# Cotton_Candy_-SCH.net
KiCad netlist of a schematic drawn in Altium Designer
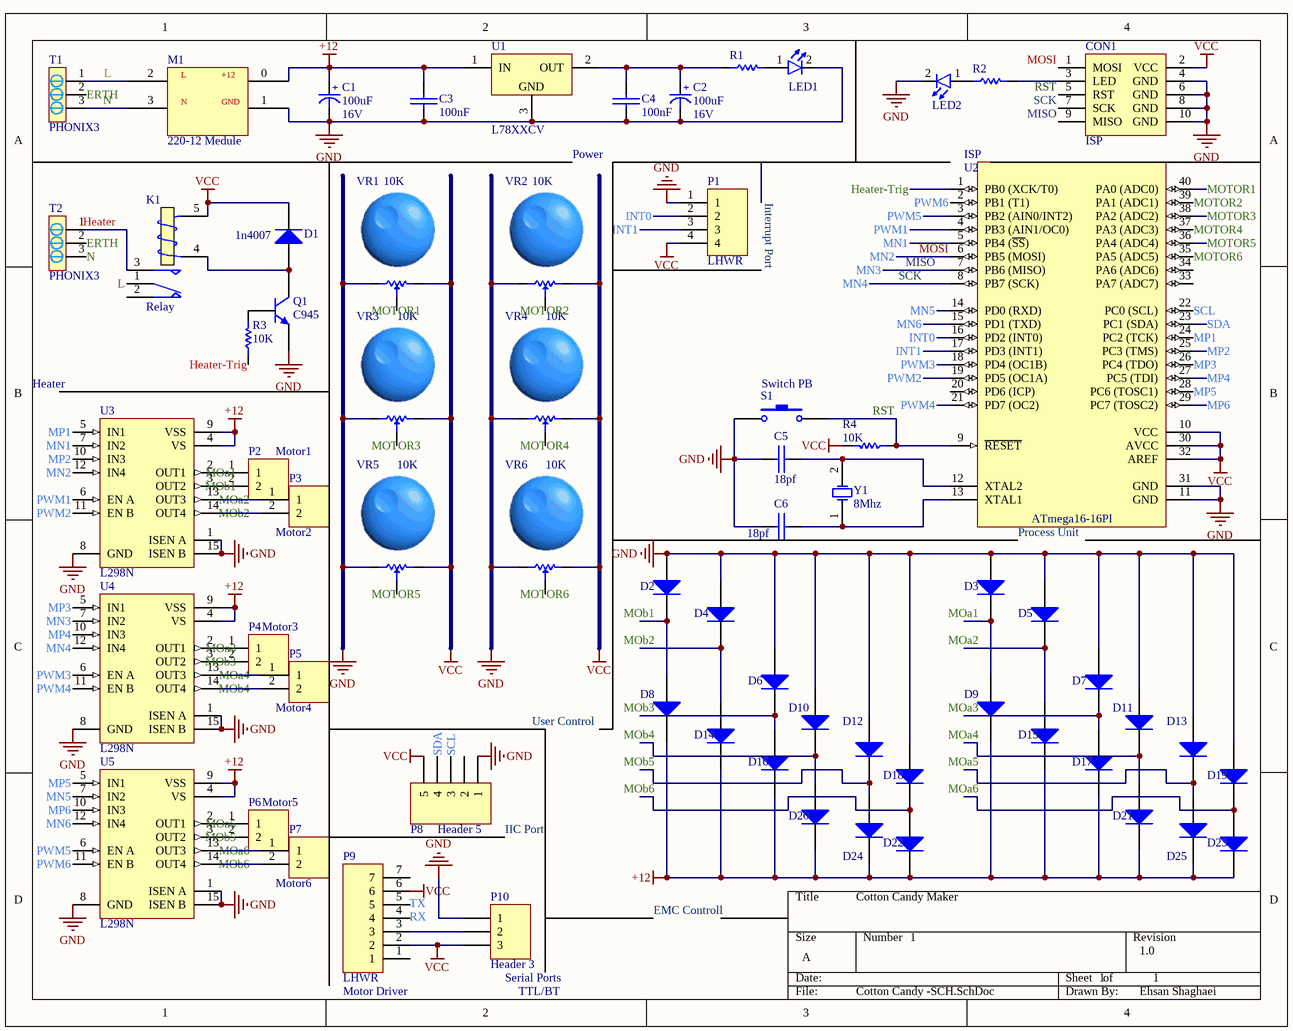
[diagram p0: Cotton Candy -SCH.SchDoc]

(export (version "E")
  (design (tool "Eeschema 10.0.6"))
  (components
    (comp (ref "C1")
      (value "100uF")
      (footprint "cap 03")
      (description "Polar Capacitor")
      (fields
        (field (name "VOLTAGE") "16V")
        (field (name "Comment") "100uf")
        (field (name "DESIGNER") "Saeid Jorablo")
      )
      (libsource (lib "My Library") (part "Cap-Polar"))
    )
    (comp (ref "C2")
      (value "100uF")
      (footprint "cap 03")
      (description "Polar Capacitor")
      (fields
        (field (name "VOLTAGE") "16V")
        (field (name "Comment") "100uf")
        (field (name "DESIGNER") "Saeid Jorablo")
      )
      (libsource (lib "My Library") (part "Cap-Polar"))
    )
    (comp (ref "C3")
      (value "100nF")
      (footprint "Cap - 10nF - 630V")
      (description "Bipolar Capacitor")
      (fields
        (field (name "VOLTAGE") "100V")
        (field (name "Comment") "100nf")
        (field (name "DESIGNER") "Saeid Jorablo")
      )
      (libsource (lib "My Library") (part "Cap-Bipolar"))
    )
    (comp (ref "C4")
      (value "100nF")
      (footprint "Cap - 10nF - 630V")
      (description "Bipolar Capacitor")
      (fields
        (field (name "VOLTAGE") "100V")
        (field (name "Comment") "100nf")
        (field (name "DESIGNER") "Saeid Jorablo")
      )
      (libsource (lib "My Library") (part "Cap-Bipolar"))
    )
    (comp (ref "C5")
      (value "18pf")
      (footprint "Cap - 10nF - 630V")
      (description "Bipolar Capacitor")
      (fields
        (field (name "VOLTAGE") "100V")
        (field (name "Comment") "22pf")
        (field (name "DESIGNER") "Saeid Jorablo")
      )
      (libsource (lib "My Library") (part "Cap-Bipolar"))
    )
    (comp (ref "C6")
      (value "18pf")
      (footprint "Cap - 10nF - 630V")
      (description "Bipolar Capacitor")
      (fields
        (field (name "VOLTAGE") "100V")
        (field (name "Comment") "22pf")
        (field (name "DESIGNER") "Saeid Jorablo")
      )
      (libsource (lib "My Library") (part "Cap-Bipolar"))
    )
    (comp (ref "CON1") (value "ISP") (footprint "IDC2_5") (libsource (lib "MyAltiumLib") (part "ISP")))
    (comp (ref "D1")
      (value "1n4007")
      (footprint "BYW98")
      (description "HIGH EFFICIENCY FAST RECOVERY RECTIFIER DIODES")
      (fields (field (name "DESIGNER") "Saeid Jorablo"))
      (libsource (lib "My Library") (part "BYW98"))
    )
    (comp (ref "D2")
      (value "~")
      (footprint "My_DO-41")
      (description "1 Amp Diode")
      (libsource (lib "Mylib") (part "1N4007"))
    )
    (comp (ref "D3")
      (value "~")
      (footprint "My_DO-41")
      (description "1 Amp Diode")
      (libsource (lib "Mylib") (part "1N4007"))
    )
    (comp (ref "D4")
      (value "~")
      (footprint "My_DO-41")
      (description "1 Amp Diode")
      (libsource (lib "Mylib") (part "1N4007"))
    )
    (comp (ref "D5")
      (value "~")
      (footprint "My_DO-41")
      (description "1 Amp Diode")
      (libsource (lib "Mylib") (part "1N4007"))
    )
    (comp (ref "D6")
      (value "~")
      (footprint "My_DO-41")
      (description "1 Amp Diode")
      (libsource (lib "Mylib") (part "1N4007"))
    )
    (comp (ref "D7")
      (value "~")
      (footprint "My_DO-41")
      (description "1 Amp Diode")
      (libsource (lib "Mylib") (part "1N4007"))
    )
    (comp (ref "D8")
      (value "~")
      (footprint "My_DO-41")
      (description "1 Amp Diode")
      (libsource (lib "Mylib") (part "1N4007"))
    )
    (comp (ref "D9")
      (value "~")
      (footprint "My_DO-41")
      (description "1 Amp Diode")
      (libsource (lib "Mylib") (part "1N4007"))
    )
    (comp (ref "D10")
      (value "~")
      (footprint "My_DO-41")
      (description "1 Amp Diode")
      (libsource (lib "Mylib") (part "1N4007"))
    )
    (comp (ref "D11")
      (value "~")
      (footprint "My_DO-41")
      (description "1 Amp Diode")
      (libsource (lib "Mylib") (part "1N4007"))
    )
    (comp (ref "D12")
      (value "~")
      (footprint "My_DO-41")
      (description "1 Amp Diode")
      (libsource (lib "Mylib") (part "1N4007"))
    )
    (comp (ref "D13")
      (value "~")
      (footprint "My_DO-41")
      (description "1 Amp Diode")
      (libsource (lib "Mylib") (part "1N4007"))
    )
    (comp (ref "D14")
      (value "~")
      (footprint "My_DO-41")
      (description "1 Amp Diode")
      (libsource (lib "Mylib") (part "1N4007"))
    )
    (comp (ref "D15")
      (value "~")
      (footprint "My_DO-41")
      (description "1 Amp Diode")
      (libsource (lib "Mylib") (part "1N4007"))
    )
    (comp (ref "D16")
      (value "~")
      (footprint "My_DO-41")
      (description "1 Amp Diode")
      (libsource (lib "Mylib") (part "1N4007"))
    )
    (comp (ref "D17")
      (value "~")
      (footprint "My_DO-41")
      (description "1 Amp Diode")
      (libsource (lib "Mylib") (part "1N4007"))
    )
    (comp (ref "D18")
      (value "~")
      (footprint "My_DO-41")
      (description "1 Amp Diode")
      (libsource (lib "Mylib") (part "1N4007"))
    )
    (comp (ref "D19")
      (value "~")
      (footprint "My_DO-41")
      (description "1 Amp Diode")
      (libsource (lib "Mylib") (part "1N4007"))
    )
    (comp (ref "D20")
      (value "~")
      (footprint "My_DO-41")
      (description "1 Amp Diode")
      (libsource (lib "Mylib") (part "1N4007"))
    )
    (comp (ref "D21")
      (value "~")
      (footprint "My_DO-41")
      (description "1 Amp Diode")
      (libsource (lib "Mylib") (part "1N4007"))
    )
    (comp (ref "D22")
      (value "~")
      (footprint "My_DO-41")
      (description "1 Amp Diode")
      (libsource (lib "Mylib") (part "1N4007"))
    )
    (comp (ref "D23")
      (value "~")
      (footprint "My_DO-41")
      (description "1 Amp Diode")
      (libsource (lib "Mylib") (part "1N4007"))
    )
    (comp (ref "D24")
      (value "~")
      (footprint "My_DO-41")
      (description "1 Amp Diode")
      (libsource (lib "Mylib") (part "1N4007"))
    )
    (comp (ref "D25")
      (value "~")
      (footprint "My_DO-41")
      (description "1 Amp Diode")
      (libsource (lib "Mylib") (part "1N4007"))
    )
    (comp (ref "K1")
      (value "Relay")
      (footprint "Relay 15.40x12.10x13.10")
      (description "SPDT Relay")
      (fields (field (name "DESIGNER") "Eng. Saeid Jorablo"))
      (libsource (lib "My Library") (part "Relay"))
    )
    (comp (ref "LED1")
      (value "red")
      (footprint "LED-3mm")
      (description "LED")
      (fields (field (name "DESIGNER") "Saeid Jorablo"))
      (libsource (lib "My Library") (part "LED"))
    )
    (comp (ref "LED2")
      (value "Yellow")
      (footprint "LED-3mm")
      (description "LED")
      (fields (field (name "DESIGNER") "Saeid Jorablo"))
      (libsource (lib "My Library") (part "LED"))
    )
    (comp (ref "M1")
      (value "220-12 Medule")
      (footprint "AC-DC 220-12")
      (libsource (lib "Soga Library") (part "220-12 Medule"))
    )
    (comp (ref "P1")
      (value "LHWR")
      (footprint "Polarized Header 4")
      (fields (field (name "DESIGNER:") "Hamed Jafarzadeh - www.R2T.ir"))
      (libsource (lib "R2T Team Library") (part "4pin LHWR"))
    )
    (comp (ref "P2")
      (value "~")
      (footprint "Polarized Header 2")
      (fields (field (name "DESIGNER:") "Hamed Jafarzadeh - www.R2T.ir"))
      (libsource (lib "R2T Team Library") (part "2pin LHWR"))
    )
    (comp (ref "P3")
      (value "~")
      (footprint "Polarized Header 2")
      (fields (field (name "DESIGNER:") "Hamed Jafarzadeh - www.R2T.ir"))
      (libsource (lib "R2T Team Library") (part "2pin LHWR"))
    )
    (comp (ref "P4")
      (value "~")
      (footprint "Polarized Header 2")
      (fields (field (name "DESIGNER:") "Hamed Jafarzadeh - www.R2T.ir"))
      (libsource (lib "R2T Team Library") (part "2pin LHWR"))
    )
    (comp (ref "P5")
      (value "~")
      (footprint "Polarized Header 2")
      (fields (field (name "DESIGNER:") "Hamed Jafarzadeh - www.R2T.ir"))
      (libsource (lib "R2T Team Library") (part "2pin LHWR"))
    )
    (comp (ref "P6")
      (value "~")
      (footprint "Polarized Header 2")
      (fields (field (name "DESIGNER:") "Hamed Jafarzadeh - www.R2T.ir"))
      (libsource (lib "R2T Team Library") (part "2pin LHWR"))
    )
    (comp (ref "P7")
      (value "~")
      (footprint "Polarized Header 2")
      (fields (field (name "DESIGNER:") "Hamed Jafarzadeh - www.R2T.ir"))
      (libsource (lib "R2T Team Library") (part "2pin LHWR"))
    )
    (comp (ref "P8")
      (value "Header 5")
      (footprint "HDR1X5")
      (description "Header, 5-Pin")
      (fields (field (name "PUBLISHER") "Altium Limited"))
      (libsource (lib "Miscellaneous Connectors") (part "Header 5"))
    )
    (comp (ref "P9")
      (value "LHWR")
      (footprint "Polarized Header 7")
      (fields (field (name "DESIGNER:") "Hamed Jafarzadeh - www.R2T.ir"))
      (libsource (lib "R2T Team Library") (part "7pin LHWR"))
    )
    (comp (ref "P10")
      (value "Header 3")
      (footprint "HDR1X3")
      (description "Header, 3-Pin")
      (fields (field (name "PUBLISHER") "Altium Limited"))
      (libsource (lib "Miscellaneous Connectors") (part "Header 3"))
    )
    (comp (ref "Q1")
      (value "C945")
      (footprint "C945")
      (description "NPN Transistor")
      (fields (field (name "DESIGNER") "Saeid Jorablo"))
      (libsource (lib "My Library") (part "C945"))
    )
    (comp (ref "R1")
      (value "330R")
      (footprint "Res-(1/4)-Stand")
      (libsource (lib "My Library") (part "Resistor"))
    )
    (comp (ref "R2")
      (value "330")
      (footprint "Res-(1/4)-Stand")
      (description "330R")
      (libsource (lib "My Library") (part "Resistor"))
    )
    (comp (ref "R3")
      (value "10K")
      (footprint "Res-(1/4)-Stand")
      (description "Resistor")
      (libsource (lib "My Library") (part "Resistor"))
    )
    (comp (ref "R4")
      (value "10K")
      (footprint "Res-(1/4)-Stand")
      (description "Resistor")
      (libsource (lib "My Library") (part "Resistor"))
    )
    (comp (ref "S1")
      (value "Switch PB")
      (footprint "Switch - Push to On")
      (description "Push Button Switch")
      (libsource (lib "My Library") (part "Switch PB"))
    )
    (comp (ref "T1") (value "PHONIX3") (footprint "PHONIX3") (libsource (lib "MyAltiumLib") (part "PHONIX3")))
    (comp (ref "T2") (value "PHONIX3") (footprint "PHONIX3") (libsource (lib "MyAltiumLib") (part "PHONIX3")))
    (comp (ref "U1")
      (value "L78XXCV")
      (footprint "78XXCV - Right")
      (description "Fixed Voltage Regulator")
      (fields (field (name "DESIGNER") "Saeid Jorablo"))
      (libsource (lib "My Library") (part "L78XXCV"))
    )
    (comp (ref "U2")
      (value "ATmega16-16PI")
      (footprint "40P6")
      (description "8-Bit AVR Microcontroller with 16K Bytes of In-System Programmable Flash Memory")
      (fields (field (name "PUBLISHER") "Altium Limited"))
      (libsource (lib "Atmel Microcontroller 8-Bit AVR") (part "ATmega16-16PI"))
    )
    (comp (ref "U3")
      (value "L298N")
      (footprint "Multiwatt15V")
      (description "Dual Full Bridge Driver")
      (fields (field (name "PUBLISHER") "Altium Limited"))
      (libsource (lib "My Library") (part "L298N"))
    )
    (comp (ref "U4")
      (value "L298N")
      (footprint "Multiwatt15V")
      (description "Dual Full Bridge Driver")
      (fields (field (name "PUBLISHER") "Altium Limited"))
      (libsource (lib "My Library") (part "L298N"))
    )
    (comp (ref "U5")
      (value "L298N")
      (footprint "Multiwatt15V")
      (description "Dual Full Bridge Driver")
      (fields (field (name "PUBLISHER") "Altium Limited"))
      (libsource (lib "My Library") (part "L298N"))
    )
    (comp (ref "VR1")
      (value "10K")
      (footprint "Setpoint POT")
      (description "Variable Resistor")
      (fields (field (name "DESIGNER") "Saeid Jorablo"))
      (libsource (lib "My Library") (part "Setpoint V"))
    )
    (comp (ref "VR2")
      (value "10K")
      (footprint "Setpoint POT")
      (description "Variable Resistor")
      (fields (field (name "DESIGNER") "Saeid Jorablo"))
      (libsource (lib "My Library") (part "Setpoint V"))
    )
    (comp (ref "VR3")
      (value "10K")
      (footprint "Setpoint POT")
      (description "Variable Resistor")
      (fields (field (name "DESIGNER") "Saeid Jorablo"))
      (libsource (lib "My Library") (part "Setpoint V"))
    )
    (comp (ref "VR4")
      (value "10K")
      (footprint "Setpoint POT")
      (description "Variable Resistor")
      (fields (field (name "DESIGNER") "Saeid Jorablo"))
      (libsource (lib "My Library") (part "Setpoint V"))
    )
    (comp (ref "VR5")
      (value "10K")
      (footprint "Setpoint POT")
      (description "Variable Resistor")
      (fields (field (name "DESIGNER") "Saeid Jorablo"))
      (libsource (lib "My Library") (part "Setpoint V"))
    )
    (comp (ref "VR6")
      (value "10K")
      (footprint "Setpoint POT")
      (description "Variable Resistor")
      (fields (field (name "DESIGNER") "Saeid Jorablo"))
      (libsource (lib "My Library") (part "Setpoint V"))
    )
    (comp (ref "Y1")
      (value "8Mhz")
      (footprint "XTAL Small")
      (description "XTAL Crystal")
      (libsource (lib "My Library") (part "XTAL"))
    )
  )
  (nets
    (net (code "1") (name "+12") (class "Default")
      (node (ref "C1") (pin "1") (pinfunction "+_1") (pintype "passive"))
      (node (ref "C3") (pin "1") (pinfunction "+_1") (pintype "passive"))
      (node (ref "D14") (pin "K") (pinfunction "K_K") (pintype "passive"))
      (node (ref "D15") (pin "K") (pinfunction "K_K") (pintype "passive"))
      (node (ref "D16") (pin "K") (pinfunction "K_K") (pintype "passive"))
      (node (ref "D17") (pin "K") (pinfunction "K_K") (pintype "passive"))
      (node (ref "D20") (pin "K") (pinfunction "K_K") (pintype "passive"))
      (node (ref "D21") (pin "K") (pinfunction "K_K") (pintype "passive"))
      (node (ref "D22") (pin "K") (pinfunction "K_K") (pintype "passive"))
      (node (ref "D23") (pin "K") (pinfunction "K_K") (pintype "passive"))
      (node (ref "D24") (pin "K") (pinfunction "K_K") (pintype "passive"))
      (node (ref "D25") (pin "K") (pinfunction "K_K") (pintype "passive"))
      (node (ref "D8") (pin "K") (pinfunction "K_K") (pintype "passive"))
      (node (ref "D9") (pin "K") (pinfunction "K_K") (pintype "passive"))
      (node (ref "M1") (pin "0") (pinfunction "0_0") (pintype "passive"))
      (node (ref "U1") (pin "1") (pinfunction "IN_1") (pintype "passive"))
      (node (ref "U3") (pin "4") (pinfunction "VS_4") (pintype "power_in"))
      (node (ref "U3") (pin "9") (pinfunction "VSS_9") (pintype "power_in"))
      (node (ref "U4") (pin "4") (pinfunction "VS_4") (pintype "power_in"))
      (node (ref "U4") (pin "9") (pinfunction "VSS_9") (pintype "power_in"))
      (node (ref "U5") (pin "4") (pinfunction "VS_4") (pintype "power_in"))
      (node (ref "U5") (pin "9") (pinfunction "VSS_9") (pintype "power_in"))
    )
    (net (code "2") (name "/ERTH") (class "Default")
      (node (ref "T1") (pin "2") (pintype "passive"))
      (node (ref "T2") (pin "2") (pintype "passive"))
    )
    (net (code "3") (name "/Heater") (class "Default")
      (node (ref "K1") (pin "3") (pinfunction "NO_3") (pintype "passive"))
      (node (ref "T2") (pin "1") (pintype "passive"))
    )
    (net (code "4") (name "/Heater-Trig") (class "Default")
      (node (ref "R3") (pin "1") (pinfunction "1_1") (pintype "passive"))
      (node (ref "U2") (pin "1") (pinfunction "PB0_(XCK/T0)_1") (pintype "bidirectional"))
    )
    (net (code "5") (name "/INT0") (class "Default")
      (node (ref "P1") (pin "2") (pinfunction "2_2") (pintype "passive"))
      (node (ref "U2") (pin "16") (pinfunction "PD2_(INT0)_16") (pintype "bidirectional"))
    )
    (net (code "6") (name "/INT1") (class "Default")
      (node (ref "P1") (pin "3") (pinfunction "3_3") (pintype "passive"))
      (node (ref "U2") (pin "17") (pinfunction "PD3_(INT1)_17") (pintype "bidirectional"))
    )
    (net (code "7") (name "/L") (class "Default")
      (node (ref "K1") (pin "1") (pinfunction "COM_1") (pintype "passive"))
      (node (ref "M1") (pin "2") (pinfunction "2_2") (pintype "passive"))
      (node (ref "T1") (pin "1") (pintype "passive"))
    )
    (net (code "8") (name "/MISO") (class "Default")
      (node (ref "CON1") (pin "9") (pinfunction "MISO_9") (pintype "passive"))
      (node (ref "U2") (pin "7") (pinfunction "PB6_(MISO)_7") (pintype "bidirectional"))
      (node (ref "U4") (pin "7") (pinfunction "IN2_7") (pintype "input"))
    )
    (net (code "9") (name "/MN1") (class "Default")
      (node (ref "U2") (pin "5") (pinfunction "PB4_(~{SS})_5") (pintype "bidirectional"))
      (node (ref "U3") (pin "7") (pinfunction "IN2_7") (pintype "input"))
    )
    (net (code "10") (name "/MN2") (class "Default")
      (node (ref "CON1") (pin "1") (pinfunction "MOSI_1") (pintype "passive"))
      (node (ref "U2") (pin "6") (pinfunction "PB5_(MOSI)_6") (pintype "bidirectional"))
      (node (ref "U3") (pin "12") (pinfunction "IN4_12") (pintype "input"))
    )
    (net (code "11") (name "/MN4") (class "Default")
      (node (ref "CON1") (pin "7") (pinfunction "SCK_7") (pintype "passive"))
      (node (ref "U2") (pin "8") (pinfunction "PB7_(SCK)_8") (pintype "bidirectional"))
      (node (ref "U4") (pin "12") (pinfunction "IN4_12") (pintype "input"))
    )
    (net (code "12") (name "/MN5") (class "Default")
      (node (ref "U2") (pin "14") (pinfunction "PD0_(RXD)_14") (pintype "bidirectional"))
      (node (ref "U5") (pin "7") (pinfunction "IN2_7") (pintype "input"))
    )
    (net (code "13") (name "/MN6") (class "Default")
      (node (ref "U2") (pin "15") (pinfunction "PD1_(TXD)_15") (pintype "bidirectional"))
      (node (ref "U5") (pin "12") (pinfunction "IN4_12") (pintype "input"))
    )
    (net (code "14") (name "/MOTOR1") (class "Default")
      (node (ref "U2") (pin "40") (pinfunction "PA0_(ADC0)_40") (pintype "bidirectional"))
      (node (ref "VR1") (pin "3") (pinfunction "SetPoint_3") (pintype "passive"))
    )
    (net (code "15") (name "/MOTOR2") (class "Default")
      (node (ref "U2") (pin "39") (pinfunction "PA1_(ADC1)_39") (pintype "bidirectional"))
      (node (ref "VR2") (pin "3") (pinfunction "SetPoint_3") (pintype "passive"))
    )
    (net (code "16") (name "/MOTOR3") (class "Default")
      (node (ref "U2") (pin "38") (pinfunction "PA2_(ADC2)_38") (pintype "bidirectional"))
      (node (ref "VR3") (pin "3") (pinfunction "SetPoint_3") (pintype "passive"))
    )
    (net (code "17") (name "/MOTOR4") (class "Default")
      (node (ref "U2") (pin "37") (pinfunction "PA3_(ADC3)_37") (pintype "bidirectional"))
      (node (ref "VR4") (pin "3") (pinfunction "SetPoint_3") (pintype "passive"))
    )
    (net (code "18") (name "/MOTOR5") (class "Default")
      (node (ref "U2") (pin "36") (pinfunction "PA4_(ADC4)_36") (pintype "bidirectional"))
      (node (ref "VR5") (pin "3") (pinfunction "SetPoint_3") (pintype "passive"))
    )
    (net (code "19") (name "/MOTOR6") (class "Default")
      (node (ref "U2") (pin "35") (pinfunction "PA5_(ADC5)_35") (pintype "bidirectional"))
      (node (ref "VR6") (pin "3") (pinfunction "SetPoint_3") (pintype "passive"))
    )
    (net (code "20") (name "/MOa1") (class "Default")
      (node (ref "D3") (pin "K") (pinfunction "K_K") (pintype "passive"))
      (node (ref "D9") (pin "A") (pinfunction "A_A") (pintype "passive"))
      (node (ref "P2") (pin "1") (pinfunction "1_1") (pintype "passive"))
      (node (ref "U3") (pin "2") (pinfunction "OUT1_2") (pintype "output"))
    )
    (net (code "21") (name "/MOa2") (class "Default")
      (node (ref "D15") (pin "A") (pinfunction "A_A") (pintype "passive"))
      (node (ref "D5") (pin "K") (pinfunction "K_K") (pintype "passive"))
      (node (ref "P3") (pin "1") (pinfunction "1_1") (pintype "passive"))
      (node (ref "U3") (pin "13") (pinfunction "OUT3_13") (pintype "output"))
    )
    (net (code "22") (name "/MOa3") (class "Default")
      (node (ref "D17") (pin "A") (pinfunction "A_A") (pintype "passive"))
      (node (ref "D7") (pin "K") (pinfunction "K_K") (pintype "passive"))
      (node (ref "P4") (pin "1") (pinfunction "1_1") (pintype "passive"))
      (node (ref "U4") (pin "2") (pinfunction "OUT1_2") (pintype "output"))
    )
    (net (code "23") (name "/MOa4") (class "Default")
      (node (ref "D11") (pin "K") (pinfunction "K_K") (pintype "passive"))
      (node (ref "D21") (pin "A") (pinfunction "A_A") (pintype "passive"))
      (node (ref "P5") (pin "1") (pinfunction "1_1") (pintype "passive"))
      (node (ref "U4") (pin "13") (pinfunction "OUT3_13") (pintype "output"))
    )
    (net (code "24") (name "/MOa5") (class "Default")
      (node (ref "D13") (pin "K") (pinfunction "K_K") (pintype "passive"))
      (node (ref "D25") (pin "A") (pinfunction "A_A") (pintype "passive"))
      (node (ref "P6") (pin "1") (pinfunction "1_1") (pintype "passive"))
      (node (ref "U5") (pin "2") (pinfunction "OUT1_2") (pintype "output"))
    )
    (net (code "25") (name "/MOa6") (class "Default")
      (node (ref "D19") (pin "K") (pinfunction "K_K") (pintype "passive"))
      (node (ref "D23") (pin "A") (pinfunction "A_A") (pintype "passive"))
      (node (ref "P7") (pin "1") (pinfunction "1_1") (pintype "passive"))
      (node (ref "U5") (pin "13") (pinfunction "OUT3_13") (pintype "output"))
    )
    (net (code "26") (name "/MOb1") (class "Default")
      (node (ref "D2") (pin "K") (pinfunction "K_K") (pintype "passive"))
      (node (ref "D8") (pin "A") (pinfunction "A_A") (pintype "passive"))
      (node (ref "P2") (pin "2") (pinfunction "2_2") (pintype "passive"))
      (node (ref "U3") (pin "3") (pinfunction "OUT2_3") (pintype "output"))
    )
    (net (code "27") (name "/MOb2") (class "Default")
      (node (ref "D14") (pin "A") (pinfunction "A_A") (pintype "passive"))
      (node (ref "D4") (pin "K") (pinfunction "K_K") (pintype "passive"))
      (node (ref "P3") (pin "2") (pinfunction "2_2") (pintype "passive"))
      (node (ref "U3") (pin "14") (pinfunction "OUT4_14") (pintype "output"))
    )
    (net (code "28") (name "/MOb3") (class "Default")
      (node (ref "D16") (pin "A") (pinfunction "A_A") (pintype "passive"))
      (node (ref "D6") (pin "K") (pinfunction "K_K") (pintype "passive"))
      (node (ref "P4") (pin "2") (pinfunction "2_2") (pintype "passive"))
      (node (ref "U4") (pin "3") (pinfunction "OUT2_3") (pintype "output"))
    )
    (net (code "29") (name "/MOb4") (class "Default")
      (node (ref "D10") (pin "K") (pinfunction "K_K") (pintype "passive"))
      (node (ref "D20") (pin "A") (pinfunction "A_A") (pintype "passive"))
      (node (ref "P5") (pin "2") (pinfunction "2_2") (pintype "passive"))
      (node (ref "U4") (pin "14") (pinfunction "OUT4_14") (pintype "output"))
    )
    (net (code "30") (name "/MOb5") (class "Default")
      (node (ref "D12") (pin "K") (pinfunction "K_K") (pintype "passive"))
      (node (ref "D24") (pin "A") (pinfunction "A_A") (pintype "passive"))
      (node (ref "P6") (pin "2") (pinfunction "2_2") (pintype "passive"))
      (node (ref "U5") (pin "3") (pinfunction "OUT2_3") (pintype "output"))
    )
    (net (code "31") (name "/MOb6") (class "Default")
      (node (ref "D18") (pin "K") (pinfunction "K_K") (pintype "passive"))
      (node (ref "D22") (pin "A") (pinfunction "A_A") (pintype "passive"))
      (node (ref "P7") (pin "2") (pinfunction "2_2") (pintype "passive"))
      (node (ref "U5") (pin "14") (pinfunction "OUT4_14") (pintype "output"))
    )
    (net (code "32") (name "/MP1") (class "Default")
      (node (ref "U2") (pin "24") (pinfunction "PC2_(TCK)_24") (pintype "bidirectional"))
      (node (ref "U3") (pin "5") (pinfunction "IN1_5") (pintype "input"))
    )
    (net (code "33") (name "/MP2") (class "Default")
      (node (ref "U2") (pin "25") (pinfunction "PC3_(TMS)_25") (pintype "bidirectional"))
      (node (ref "U3") (pin "10") (pinfunction "IN3_10") (pintype "input"))
    )
    (net (code "34") (name "/MP3") (class "Default")
      (node (ref "U2") (pin "26") (pinfunction "PC4_(TDO)_26") (pintype "bidirectional"))
      (node (ref "U4") (pin "5") (pinfunction "IN1_5") (pintype "input"))
    )
    (net (code "35") (name "/MP4") (class "Default")
      (node (ref "U2") (pin "27") (pinfunction "PC5_(TDI)_27") (pintype "bidirectional"))
      (node (ref "U4") (pin "10") (pinfunction "IN3_10") (pintype "input"))
    )
    (net (code "36") (name "/MP5") (class "Default")
      (node (ref "U2") (pin "28") (pinfunction "PC6_(TOSC1)_28") (pintype "bidirectional"))
      (node (ref "U5") (pin "5") (pinfunction "IN1_5") (pintype "input"))
    )
    (net (code "37") (name "/MP6") (class "Default")
      (node (ref "U2") (pin "29") (pinfunction "PC7_(TOSC2)_29") (pintype "bidirectional"))
      (node (ref "U5") (pin "10") (pinfunction "IN3_10") (pintype "input"))
    )
    (net (code "38") (name "/N") (class "Default")
      (node (ref "M1") (pin "3") (pinfunction "3_3") (pintype "passive"))
      (node (ref "T1") (pin "3") (pintype "passive"))
      (node (ref "T2") (pin "3") (pintype "passive"))
    )
    (net (code "39") (name "/PWM1") (class "Default")
      (node (ref "U2") (pin "4") (pinfunction "PB3_(AIN1/OC0)_4") (pintype "bidirectional"))
      (node (ref "U3") (pin "6") (pinfunction "EN_A_6") (pintype "input"))
    )
    (net (code "40") (name "/PWM2") (class "Default")
      (node (ref "U2") (pin "19") (pinfunction "PD5_(OC1A)_19") (pintype "bidirectional"))
      (node (ref "U3") (pin "11") (pinfunction "EN_B_11") (pintype "input"))
    )
    (net (code "41") (name "/PWM3") (class "Default")
      (node (ref "U2") (pin "18") (pinfunction "PD4_(OC1B)_18") (pintype "bidirectional"))
      (node (ref "U4") (pin "6") (pinfunction "EN_A_6") (pintype "input"))
    )
    (net (code "42") (name "/PWM4") (class "Default")
      (node (ref "U2") (pin "21") (pinfunction "PD7_(OC2)_21") (pintype "bidirectional"))
      (node (ref "U4") (pin "11") (pinfunction "EN_B_11") (pintype "input"))
    )
    (net (code "43") (name "/PWM5") (class "Default")
      (node (ref "U2") (pin "3") (pinfunction "PB2_(AIN0/INT2)_3") (pintype "bidirectional"))
      (node (ref "U5") (pin "6") (pinfunction "EN_A_6") (pintype "input"))
    )
    (net (code "44") (name "/PWM6") (class "Default")
      (node (ref "U2") (pin "2") (pinfunction "PB1_(T1)_2") (pintype "bidirectional"))
      (node (ref "U5") (pin "11") (pinfunction "EN_B_11") (pintype "input"))
    )
    (net (code "45") (name "/RST") (class "Default")
      (node (ref "CON1") (pin "5") (pinfunction "RST_5") (pintype "passive"))
      (node (ref "R4") (pin "1") (pinfunction "1_1") (pintype "passive"))
      (node (ref "S1") (pin "2") (pinfunction "2_2") (pintype "passive"))
      (node (ref "U2") (pin "9") (pinfunction "~{RESET}_9") (pintype "input"))
    )
    (net (code "47") (name "/SCL") (class "Default")
      (node (ref "P8") (pin "3") (pinfunction "3_3") (pintype "passive"))
      (node (ref "U2") (pin "22") (pinfunction "PC0_(SCL)_22") (pintype "bidirectional"))
    )
    (net (code "48") (name "/SDA") (class "Default")
      (node (ref "P8") (pin "4") (pinfunction "4_4") (pintype "passive"))
      (node (ref "U2") (pin "23") (pinfunction "PC1_(SDA)_23") (pintype "bidirectional"))
    )
    (net (code "50") (name "GND") (class "Default")
      (node (ref "C1") (pin "2") (pinfunction "-_2") (pintype "passive"))
      (node (ref "C2") (pin "2") (pinfunction "-_2") (pintype "passive"))
      (node (ref "C3") (pin "2") (pinfunction "-_2") (pintype "passive"))
      (node (ref "C4") (pin "2") (pinfunction "-_2") (pintype "passive"))
      (node (ref "C5") (pin "2") (pinfunction "-_2") (pintype "passive"))
      (node (ref "C6") (pin "2") (pinfunction "-_2") (pintype "passive"))
      (node (ref "CON1") (pin "10") (pinfunction "GND_10") (pintype "passive"))
      (node (ref "CON1") (pin "4") (pinfunction "GND_4") (pintype "passive"))
      (node (ref "CON1") (pin "6") (pinfunction "GND_6") (pintype "passive"))
      (node (ref "CON1") (pin "8") (pinfunction "GND_8") (pintype "passive"))
      (node (ref "D10") (pin "A") (pinfunction "A_A") (pintype "passive"))
      (node (ref "D11") (pin "A") (pinfunction "A_A") (pintype "passive"))
      (node (ref "D12") (pin "A") (pinfunction "A_A") (pintype "passive"))
      (node (ref "D13") (pin "A") (pinfunction "A_A") (pintype "passive"))
      (node (ref "D18") (pin "A") (pinfunction "A_A") (pintype "passive"))
      (node (ref "D19") (pin "A") (pinfunction "A_A") (pintype "passive"))
      (node (ref "D2") (pin "A") (pinfunction "A_A") (pintype "passive"))
      (node (ref "D3") (pin "A") (pinfunction "A_A") (pintype "passive"))
      (node (ref "D4") (pin "A") (pinfunction "A_A") (pintype "passive"))
      (node (ref "D5") (pin "A") (pinfunction "A_A") (pintype "passive"))
      (node (ref "D6") (pin "A") (pinfunction "A_A") (pintype "passive"))
      (node (ref "D7") (pin "A") (pinfunction "A_A") (pintype "passive"))
      (node (ref "LED1") (pin "2") (pinfunction "K_2") (pintype "passive"))
      (node (ref "LED2") (pin "2") (pinfunction "K_2") (pintype "passive"))
      (node (ref "M1") (pin "1") (pinfunction "1_1") (pintype "passive"))
      (node (ref "P1") (pin "1") (pinfunction "1_1") (pintype "passive"))
      (node (ref "P10") (pin "1") (pinfunction "1_1") (pintype "passive"))
      (node (ref "P8") (pin "1") (pinfunction "1_1") (pintype "passive"))
      (node (ref "Q1") (pin "1") (pinfunction "E_1") (pintype "passive"))
      (node (ref "S1") (pin "1") (pinfunction "1_1") (pintype "passive"))
      (node (ref "U1") (pin "3") (pinfunction "GND_3") (pintype "passive"))
      (node (ref "U2") (pin "11") (pinfunction "GND_11") (pintype "power_in"))
      (node (ref "U2") (pin "31") (pinfunction "GND_31") (pintype "power_in"))
      (node (ref "U3") (pin "1") (pinfunction "ISEN_A_1") (pintype "passive"))
      (node (ref "U3") (pin "15") (pinfunction "ISEN_B_15") (pintype "passive"))
      (node (ref "U3") (pin "8") (pinfunction "GND_8") (pintype "power_in"))
      (node (ref "U4") (pin "1") (pinfunction "ISEN_A_1") (pintype "passive"))
      (node (ref "U4") (pin "15") (pinfunction "ISEN_B_15") (pintype "passive"))
      (node (ref "U4") (pin "8") (pinfunction "GND_8") (pintype "power_in"))
      (node (ref "U5") (pin "1") (pinfunction "ISEN_A_1") (pintype "passive"))
      (node (ref "U5") (pin "15") (pinfunction "ISEN_B_15") (pintype "passive"))
      (node (ref "U5") (pin "8") (pinfunction "GND_8") (pintype "power_in"))
      (node (ref "VR1") (pin "1") (pinfunction "CCW_1") (pintype "passive"))
      (node (ref "VR2") (pin "1") (pinfunction "CCW_1") (pintype "passive"))
      (node (ref "VR3") (pin "1") (pinfunction "CCW_1") (pintype "passive"))
      (node (ref "VR4") (pin "1") (pinfunction "CCW_1") (pintype "passive"))
      (node (ref "VR5") (pin "1") (pinfunction "CCW_1") (pintype "passive"))
      (node (ref "VR6") (pin "1") (pinfunction "CCW_1") (pintype "passive"))
    )
    (net (code "51") (name "Net-(C2-+)") (class "Default")
      (node (ref "C2") (pin "1") (pinfunction "+_1") (pintype "passive"))
      (node (ref "C4") (pin "1") (pinfunction "+_1") (pintype "passive"))
      (node (ref "R1") (pin "1") (pinfunction "1_1") (pintype "passive"))
      (node (ref "U1") (pin "2") (pinfunction "OUT_2") (pintype "passive"))
    )
    (net (code "52") (name "Net-(C5-+)") (class "Default")
      (node (ref "C5") (pin "1") (pinfunction "+_1") (pintype "passive"))
      (node (ref "U2") (pin "12") (pinfunction "XTAL2_12") (pintype "passive"))
      (node (ref "Y1") (pin "2") (pinfunction "OSC2_2") (pintype "passive"))
    )
    (net (code "53") (name "Net-(C6-+)") (class "Default")
      (node (ref "C6") (pin "1") (pinfunction "+_1") (pintype "passive"))
      (node (ref "U2") (pin "13") (pinfunction "XTAL1_13") (pintype "passive"))
      (node (ref "Y1") (pin "1") (pinfunction "OSC1_1") (pintype "passive"))
    )
    (net (code "54") (name "Net-(CON1-LED)") (class "Default")
      (node (ref "CON1") (pin "3") (pinfunction "LED_3") (pintype "passive"))
      (node (ref "R2") (pin "2") (pinfunction "2_2") (pintype "passive"))
    )
    (net (code "55") (name "Net-(D1-A)") (class "Default")
      (node (ref "D1") (pin "1") (pinfunction "A_1") (pintype "passive"))
      (node (ref "K1") (pin "4") (pinfunction "T1_4") (pintype "passive"))
      (node (ref "Q1") (pin "2") (pinfunction "C_2") (pintype "passive"))
    )
    (net (code "56") (name "Net-(LED1-A)") (class "Default")
      (node (ref "LED1") (pin "1") (pinfunction "A_1") (pintype "passive"))
      (node (ref "R1") (pin "2") (pinfunction "2_2") (pintype "passive"))
    )
    (net (code "57") (name "Net-(LED2-A)") (class "Default")
      (node (ref "LED2") (pin "1") (pinfunction "A_1") (pintype "passive"))
      (node (ref "R2") (pin "1") (pinfunction "1_1") (pintype "passive"))
    )
    (net (code "58") (name "Net-(P10-Pad2)") (class "Default")
      (node (ref "P10") (pin "2") (pinfunction "2_2") (pintype "passive"))
      (node (ref "P9") (pin "3") (pinfunction "3_3") (pintype "passive"))
    )
    (net (code "59") (name "Net-(Q1-B)") (class "Default")
      (node (ref "Q1") (pin "3") (pinfunction "B_3") (pintype "passive"))
      (node (ref "R3") (pin "2") (pinfunction "2_2") (pintype "passive"))
    )
    (net (code "60") (name "VCC") (class "Default")
      (node (ref "CON1") (pin "2") (pinfunction "VCC_2") (pintype "passive"))
      (node (ref "D1") (pin "2") (pinfunction "K_2") (pintype "passive"))
      (node (ref "K1") (pin "5") (pinfunction "T2_5") (pintype "passive"))
      (node (ref "P1") (pin "4") (pinfunction "4_4") (pintype "passive"))
      (node (ref "P10") (pin "3") (pinfunction "3_3") (pintype "passive"))
      (node (ref "P8") (pin "5") (pinfunction "5_5") (pintype "passive"))
      (node (ref "P9") (pin "2") (pinfunction "2_2") (pintype "passive"))
      (node (ref "P9") (pin "6") (pinfunction "6_6") (pintype "passive"))
      (node (ref "R4") (pin "2") (pinfunction "2_2") (pintype "passive"))
      (node (ref "U2") (pin "10") (pinfunction "VCC_10") (pintype "power_in"))
      (node (ref "U2") (pin "30") (pinfunction "AVCC_30") (pintype "power_in"))
      (node (ref "U2") (pin "32") (pinfunction "AREF_32") (pintype "passive"))
      (node (ref "VR1") (pin "2") (pinfunction "CW_2") (pintype "passive"))
      (node (ref "VR2") (pin "2") (pinfunction "CW_2") (pintype "passive"))
      (node (ref "VR3") (pin "2") (pinfunction "CW_2") (pintype "passive"))
      (node (ref "VR4") (pin "2") (pinfunction "CW_2") (pintype "passive"))
      (node (ref "VR5") (pin "2") (pinfunction "CW_2") (pintype "passive"))
      (node (ref "VR6") (pin "2") (pinfunction "CW_2") (pintype "passive"))
    )
    (net (code "61") (name "unconnected-(K1-NC-Pad2)") (class "Default")
      (node (ref "K1") (pin "2") (pinfunction "NC_2") (pintype "passive"))
    )
    (net (code "62") (name "unconnected-(P8-Pad2)") (class "Default")
      (node (ref "P8") (pin "2") (pinfunction "2_2") (pintype "passive"))
    )
    (net (code "63") (name "unconnected-(P9-Pad1)") (class "Default")
      (node (ref "P9") (pin "1") (pinfunction "1_1") (pintype "passive"))
    )
    (net (code "64") (name "unconnected-(P9-Pad4)") (class "Default")
      (node (ref "P9") (pin "4") (pinfunction "4_4") (pintype "passive"))
    )
    (net (code "65") (name "unconnected-(P9-Pad5)") (class "Default")
      (node (ref "P9") (pin "5") (pinfunction "5_5") (pintype "passive"))
    )
    (net (code "66") (name "unconnected-(P9-Pad7)") (class "Default")
      (node (ref "P9") (pin "7") (pinfunction "7_7") (pintype "passive"))
    )
    (net (code "67") (name "unconnected-(U2-PA6_(ADC6)-Pad34)") (class "Default")
      (node (ref "U2") (pin "34") (pinfunction "PA6_(ADC6)_34") (pintype "bidirectional"))
    )
    (net (code "68") (name "unconnected-(U2-PA7_(ADC7)-Pad33)") (class "Default")
      (node (ref "U2") (pin "33") (pinfunction "PA7_(ADC7)_33") (pintype "bidirectional"))
    )
    (net (code "69") (name "unconnected-(U2-PD6_(ICP)-Pad20)") (class "Default")
      (node (ref "U2") (pin "20") (pinfunction "PD6_(ICP)_20") (pintype "bidirectional"))
    )
  )
)
